# PowerSupply_Schematic.net
KiCad netlist of a schematic drawn in Altium Designer
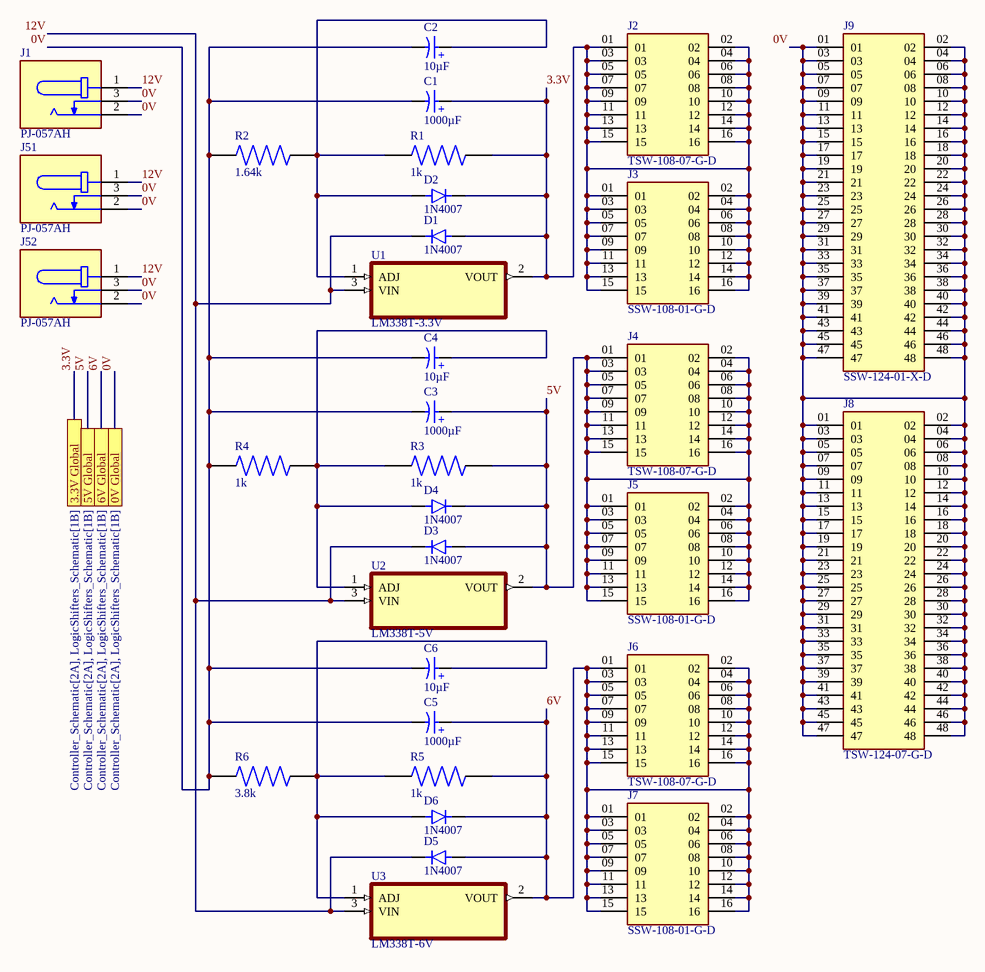
[diagram p0: PowerSupply_Schematic.SchDoc]

(export (version "E")
  (design (tool "Eeschema 10.0.6"))
  (components
    (comp (ref "C1")
      (value "1000µF")
      (footprint "WCAP-ATG5_D10H12.5")
      (description "WCAP-ATG5 Aluminum Electrolytic Capacitor, Radial, THT, D10 x H12.5mm, 1000µF, 16V")
      (fields
        (field (name "MANUFACTURER PART NUMBER") "860020375017")
        (field (name "MANUFACTURER") "Wurth Elektronik")
      )
      (libsource (lib "CAP-DIP-1000uF-16V") (part "860020375017"))
    )
    (comp (ref "C2")
      (value "10µF")
      (footprint "WCAP-ATG5_D5H11")
      (description "WCAP-ATG5 Aluminum Electrolytic Capacitor, Radial, THT, D5 x H11mm, 10µF, 16V")
      (fields
        (field (name "MANUFACTURER PART NUMBER") "860020372001")
        (field (name "MANUFACTURER") "Wurth Elektronik")
      )
      (libsource (lib "CAP-DIP-1000uF-16V") (part "860020372001"))
    )
    (comp (ref "C3")
      (value "1000µF")
      (footprint "WCAP-ATG5_D10H12.5")
      (description "WCAP-ATG5 Aluminum Electrolytic Capacitor, Radial, THT, D10 x H12.5mm, 1000µF, 16V")
      (fields
        (field (name "MANUFACTURER PART NUMBER") "860020375017")
        (field (name "MANUFACTURER") "Wurth Elektronik")
      )
      (libsource (lib "CAP-DIP-1000uF-16V") (part "860020375017"))
    )
    (comp (ref "C4")
      (value "10µF")
      (footprint "WCAP-ATG5_D5H11")
      (description "WCAP-ATG5 Aluminum Electrolytic Capacitor, Radial, THT, D5 x H11mm, 10µF, 16V")
      (fields
        (field (name "MANUFACTURER PART NUMBER") "860020372001")
        (field (name "MANUFACTURER") "Wurth Elektronik")
      )
      (libsource (lib "CAP-DIP-1000uF-16V") (part "860020372001"))
    )
    (comp (ref "C5")
      (value "1000µF")
      (footprint "WCAP-ATG5_D10H12.5")
      (description "WCAP-ATG5 Aluminum Electrolytic Capacitor, Radial, THT, D10 x H12.5mm, 1000µF, 16V")
      (fields
        (field (name "MANUFACTURER PART NUMBER") "860020375017")
        (field (name "MANUFACTURER") "Wurth Elektronik")
      )
      (libsource (lib "CAP-DIP-1000uF-16V") (part "860020375017"))
    )
    (comp (ref "C6")
      (value "10µF")
      (footprint "WCAP-ATG5_D5H11")
      (description "WCAP-ATG5 Aluminum Electrolytic Capacitor, Radial, THT, D5 x H11mm, 10µF, 16V")
      (fields
        (field (name "MANUFACTURER PART NUMBER") "860020372001")
        (field (name "MANUFACTURER") "Wurth Elektronik")
      )
      (libsource (lib "CAP-DIP-1000uF-16V") (part "860020372001"))
    )
    (comp (ref "D1")
      (value "1N4007")
      (footprint "DIOAD1060W80L520D270")
      (description "Rectifier Silicon, 1000V, 1 A, DO-41 Case, Solder Leads, 1N Series ¦ NTE Electronics Inc. 1N4007")
      (fields (field (name "MF") "NTE Electronics, Inc."))
      (libsource (lib "DO-41") (part "1N4007"))
    )
    (comp (ref "D2")
      (value "1N4007")
      (footprint "DIOAD1060W80L520D270")
      (description "Rectifier Silicon, 1000V, 1 A, DO-41 Case, Solder Leads, 1N Series ¦ NTE Electronics Inc. 1N4007")
      (fields (field (name "MF") "NTE Electronics, Inc."))
      (libsource (lib "DO-41") (part "1N4007"))
    )
    (comp (ref "D3")
      (value "1N4007")
      (footprint "DIOAD1060W80L520D270")
      (description "Rectifier Silicon, 1000V, 1 A, DO-41 Case, Solder Leads, 1N Series ¦ NTE Electronics Inc. 1N4007")
      (fields (field (name "MF") "NTE Electronics, Inc."))
      (libsource (lib "DO-41") (part "1N4007"))
    )
    (comp (ref "D4")
      (value "1N4007")
      (footprint "DIOAD1060W80L520D270")
      (description "Rectifier Silicon, 1000V, 1 A, DO-41 Case, Solder Leads, 1N Series ¦ NTE Electronics Inc. 1N4007")
      (fields (field (name "MF") "NTE Electronics, Inc."))
      (libsource (lib "DO-41") (part "1N4007"))
    )
    (comp (ref "D5")
      (value "1N4007")
      (footprint "DIOAD1060W80L520D270")
      (description "Rectifier Silicon, 1000V, 1 A, DO-41 Case, Solder Leads, 1N Series ¦ NTE Electronics Inc. 1N4007")
      (fields (field (name "MF") "NTE Electronics, Inc."))
      (libsource (lib "DO-41") (part "1N4007"))
    )
    (comp (ref "D6")
      (value "1N4007")
      (footprint "DIOAD1060W80L520D270")
      (description "Rectifier Silicon, 1000V, 1 A, DO-41 Case, Solder Leads, 1N Series ¦ NTE Electronics Inc. 1N4007")
      (fields (field (name "MF") "NTE Electronics, Inc."))
      (libsource (lib "DO-41") (part "1N4007"))
    )
    (comp (ref "J1")
      (value "PJ-057AH")
      (footprint "CUI_PJ-057AH")
      (description "2.0 x 6.3 mm, 5.0 A, Horizontal, Through Hole, Pick-n-Place Top, Dc Power Jack Connector")
      (fields (field (name "MF") "Same Sky"))
      (libsource (lib "PowerJack-2mm-6.3mm") (part "PJ-057AH"))
    )
    (comp (ref "J2")
      (value "TSW-108-07-G-D")
      (footprint "SAMTEC_TSW-108-07-G-D")
      (fields (field (name "MF") "Samtec"))
      (libsource (lib "TSW-108-07-G-D") (part "TSW-108-07-G-D"))
    )
    (comp (ref "J3")
      (value "SSW-108-01-G-D")
      (footprint "SAMTEC_SSW-108-01-G-D")
      (fields (field (name "MF") "Samtec"))
      (libsource (lib "SSW-108-01-G-D") (part "SSW-108-01-G-D"))
    )
    (comp (ref "J4")
      (value "TSW-108-07-G-D")
      (footprint "SAMTEC_TSW-108-07-G-D")
      (fields (field (name "MF") "Samtec"))
      (libsource (lib "TSW-108-07-G-D") (part "TSW-108-07-G-D"))
    )
    (comp (ref "J5")
      (value "SSW-108-01-G-D")
      (footprint "SAMTEC_SSW-108-01-G-D")
      (fields (field (name "MF") "Samtec"))
      (libsource (lib "SSW-108-01-G-D") (part "SSW-108-01-G-D"))
    )
    (comp (ref "J6")
      (value "TSW-108-07-G-D")
      (footprint "SAMTEC_TSW-108-07-G-D")
      (fields (field (name "MF") "Samtec"))
      (libsource (lib "TSW-108-07-G-D") (part "TSW-108-07-G-D"))
    )
    (comp (ref "J7")
      (value "SSW-108-01-G-D")
      (footprint "SAMTEC_SSW-108-01-G-D")
      (fields (field (name "MF") "Samtec"))
      (libsource (lib "SSW-108-01-G-D") (part "SSW-108-01-G-D"))
    )
    (comp (ref "J8")
      (value "TSW-124-07-G-D")
      (footprint "SAMTEC_TSW-124-07-G-D")
      (fields (field (name "MF") "Samtec"))
      (libsource (lib "TSW-124-07-G-D") (part "TSW-124-07-G-D"))
    )
    (comp (ref "J9")
      (value "SSW-124-01-X-D")
      (footprint "SAMTEC_SSW-124-01-X-D")
      (fields (field (name "MF") "Samtec"))
      (libsource (lib "SSW-124-01-G-D") (part "SSW-124-01-X-D"))
    )
    (comp (ref "J51")
      (value "PJ-057AH")
      (footprint "CUI_PJ-057AH")
      (description "2.0 x 6.3 mm, 5.0 A, Horizontal, Through Hole, Pick-n-Place Top, Dc Power Jack Connector")
      (fields (field (name "MF") "Same Sky"))
      (libsource (lib "PowerJack-2mm-6.3mm") (part "PJ-057AH"))
    )
    (comp (ref "J52")
      (value "PJ-057AH")
      (footprint "CUI_PJ-057AH")
      (description "2.0 x 6.3 mm, 5.0 A, Horizontal, Through Hole, Pick-n-Place Top, Dc Power Jack Connector")
      (fields (field (name "MF") "Same Sky"))
      (libsource (lib "PowerJack-2mm-6.3mm") (part "PJ-057AH"))
    )
    (comp (ref "R1")
      (value "1k")
      (footprint "RESAD700W45L350D185")
      (description "1 MOhms Â±5% 0.25W, 1/4W Through Hole Resistor Axial - Carbon Film")
      (fields (field (name "MF") "TE Connectivity") (field (name "MP") "3-1623927-1"))
      (libsource (lib "RES-DIP-0.25W") (part "3-1623927-1"))
    )
    (comp (ref "R2")
      (value "1.64k")
      (footprint "RESAD700W45L350D185")
      (description "1 MOhms Â±5% 0.25W, 1/4W Through Hole Resistor Axial - Carbon Film")
      (fields (field (name "MF") "TE Connectivity") (field (name "MP") "3-1623927-1"))
      (libsource (lib "RES-DIP-0.25W") (part "3-1623927-1"))
    )
    (comp (ref "R3")
      (value "1k")
      (footprint "RESAD700W45L350D185")
      (description "1 MOhms Â±5% 0.25W, 1/4W Through Hole Resistor Axial - Carbon Film")
      (fields (field (name "MF") "TE Connectivity") (field (name "MP") "3-1623927-1"))
      (libsource (lib "RES-DIP-0.25W") (part "3-1623927-1"))
    )
    (comp (ref "R4")
      (value "1k")
      (footprint "RESAD700W45L350D185")
      (description "1 MOhms Â±5% 0.25W, 1/4W Through Hole Resistor Axial - Carbon Film")
      (fields (field (name "MF") "TE Connectivity") (field (name "MP") "3-1623927-1"))
      (libsource (lib "RES-DIP-0.25W") (part "3-1623927-1"))
    )
    (comp (ref "R5")
      (value "1k")
      (footprint "RESAD700W45L350D185")
      (description "1 MOhms Â±5% 0.25W, 1/4W Through Hole Resistor Axial - Carbon Film")
      (fields (field (name "MF") "TE Connectivity") (field (name "MP") "3-1623927-1"))
      (libsource (lib "RES-DIP-0.25W") (part "3-1623927-1"))
    )
    (comp (ref "R6")
      (value "3.8k")
      (footprint "RESAD700W45L350D185")
      (description "1 MOhms Â±5% 0.25W, 1/4W Through Hole Resistor Axial - Carbon Film")
      (fields (field (name "MF") "TE Connectivity") (field (name "MP") "3-1623927-1"))
      (libsource (lib "RES-DIP-0.25W") (part "3-1623927-1"))
    )
    (comp (ref "U1")
      (value "LM338T-3.3V")
      (footprint "TO254P1054X470X1955-3")
      (description "5-A, 40-V, low-IQ, adjustable linear voltage regulator 3-TO-220 0 to 125")
      (fields (field (name "MF") "Texas Instruments") (field (name "MP") "LM338T"))
      (libsource (lib "LM338T") (part "LM338T"))
    )
    (comp (ref "U2")
      (value "LM338T-5V")
      (footprint "TO254P1054X470X1955-3")
      (description "5-A, 40-V, low-IQ, adjustable linear voltage regulator 3-TO-220 0 to 125")
      (fields (field (name "MF") "Texas Instruments") (field (name "MP") "LM338T"))
      (libsource (lib "LM338T") (part "LM338T"))
    )
    (comp (ref "U3")
      (value "LM338T-6V")
      (footprint "TO254P1054X470X1955-3")
      (description "5-A, 40-V, low-IQ, adjustable linear voltage regulator 3-TO-220 0 to 125")
      (fields (field (name "MF") "Texas Instruments") (field (name "MP") "LM338T"))
      (libsource (lib "LM338T") (part "LM338T"))
    )
  )
  (nets
    (net (code "1") (name "/0V") (class "Default")
      (node (ref "C1") (pin "2") (pinfunction "N_2") (pintype "passive"))
      (node (ref "C2") (pin "2") (pinfunction "N_2") (pintype "passive"))
      (node (ref "C3") (pin "2") (pinfunction "N_2") (pintype "passive"))
      (node (ref "C4") (pin "2") (pinfunction "N_2") (pintype "passive"))
      (node (ref "C5") (pin "2") (pinfunction "N_2") (pintype "passive"))
      (node (ref "C6") (pin "2") (pinfunction "N_2") (pintype "passive"))
      (node (ref "J1") (pin "2") (pinfunction "2_2") (pintype "passive"))
      (node (ref "J1") (pin "3") (pinfunction "3_3") (pintype "passive"))
      (node (ref "J51") (pin "2") (pinfunction "2_2") (pintype "passive"))
      (node (ref "J51") (pin "3") (pinfunction "3_3") (pintype "passive"))
      (node (ref "J52") (pin "2") (pinfunction "2_2") (pintype "passive"))
      (node (ref "J52") (pin "3") (pinfunction "3_3") (pintype "passive"))
      (node (ref "J8") (pin "01") (pinfunction "01_01") (pintype "passive"))
      (node (ref "J8") (pin "02") (pinfunction "02_02") (pintype "passive"))
      (node (ref "J8") (pin "03") (pinfunction "03_03") (pintype "passive"))
      (node (ref "J8") (pin "04") (pinfunction "04_04") (pintype "passive"))
      (node (ref "J8") (pin "05") (pinfunction "05_05") (pintype "passive"))
      (node (ref "J8") (pin "06") (pinfunction "06_06") (pintype "passive"))
      (node (ref "J8") (pin "07") (pinfunction "07_07") (pintype "passive"))
      (node (ref "J8") (pin "08") (pinfunction "08_08") (pintype "passive"))
      (node (ref "J8") (pin "09") (pinfunction "09_09") (pintype "passive"))
      (node (ref "J8") (pin "10") (pinfunction "10_10") (pintype "passive"))
      (node (ref "J8") (pin "11") (pinfunction "11_11") (pintype "passive"))
      (node (ref "J8") (pin "12") (pinfunction "12_12") (pintype "passive"))
      (node (ref "J8") (pin "13") (pinfunction "13_13") (pintype "passive"))
      (node (ref "J8") (pin "14") (pinfunction "14_14") (pintype "passive"))
      (node (ref "J8") (pin "15") (pinfunction "15_15") (pintype "passive"))
      (node (ref "J8") (pin "16") (pinfunction "16_16") (pintype "passive"))
      (node (ref "J8") (pin "17") (pinfunction "17_17") (pintype "passive"))
      (node (ref "J8") (pin "18") (pinfunction "18_18") (pintype "passive"))
      (node (ref "J8") (pin "19") (pinfunction "19_19") (pintype "passive"))
      (node (ref "J8") (pin "20") (pinfunction "20_20") (pintype "passive"))
      (node (ref "J8") (pin "21") (pinfunction "21_21") (pintype "passive"))
      (node (ref "J8") (pin "22") (pinfunction "22_22") (pintype "passive"))
      (node (ref "J8") (pin "23") (pinfunction "23_23") (pintype "passive"))
      (node (ref "J8") (pin "24") (pinfunction "24_24") (pintype "passive"))
      (node (ref "J8") (pin "25") (pinfunction "25_25") (pintype "passive"))
      (node (ref "J8") (pin "26") (pinfunction "26_26") (pintype "passive"))
      (node (ref "J8") (pin "27") (pinfunction "27_27") (pintype "passive"))
      (node (ref "J8") (pin "28") (pinfunction "28_28") (pintype "passive"))
      (node (ref "J8") (pin "29") (pinfunction "29_29") (pintype "passive"))
      (node (ref "J8") (pin "30") (pinfunction "30_30") (pintype "passive"))
      (node (ref "J8") (pin "31") (pinfunction "31_31") (pintype "passive"))
      (node (ref "J8") (pin "32") (pinfunction "32_32") (pintype "passive"))
      (node (ref "J8") (pin "33") (pinfunction "33_33") (pintype "passive"))
      (node (ref "J8") (pin "34") (pinfunction "34_34") (pintype "passive"))
      (node (ref "J8") (pin "35") (pinfunction "35_35") (pintype "passive"))
      (node (ref "J8") (pin "36") (pinfunction "36_36") (pintype "passive"))
      (node (ref "J8") (pin "37") (pinfunction "37_37") (pintype "passive"))
      (node (ref "J8") (pin "38") (pinfunction "38_38") (pintype "passive"))
      (node (ref "J8") (pin "39") (pinfunction "39_39") (pintype "passive"))
      (node (ref "J8") (pin "40") (pinfunction "40_40") (pintype "passive"))
      (node (ref "J8") (pin "41") (pinfunction "41_41") (pintype "passive"))
      (node (ref "J8") (pin "42") (pinfunction "42_42") (pintype "passive"))
      (node (ref "J8") (pin "43") (pinfunction "43_43") (pintype "passive"))
      (node (ref "J8") (pin "44") (pinfunction "44_44") (pintype "passive"))
      (node (ref "J8") (pin "45") (pinfunction "45_45") (pintype "passive"))
      (node (ref "J8") (pin "46") (pinfunction "46_46") (pintype "passive"))
      (node (ref "J8") (pin "47") (pinfunction "47_47") (pintype "passive"))
      (node (ref "J8") (pin "48") (pinfunction "48_48") (pintype "passive"))
      (node (ref "J9") (pin "01") (pinfunction "01_01") (pintype "passive"))
      (node (ref "J9") (pin "02") (pinfunction "02_02") (pintype "passive"))
      (node (ref "J9") (pin "03") (pinfunction "03_03") (pintype "passive"))
      (node (ref "J9") (pin "04") (pinfunction "04_04") (pintype "passive"))
      (node (ref "J9") (pin "05") (pinfunction "05_05") (pintype "passive"))
      (node (ref "J9") (pin "06") (pinfunction "06_06") (pintype "passive"))
      (node (ref "J9") (pin "07") (pinfunction "07_07") (pintype "passive"))
      (node (ref "J9") (pin "08") (pinfunction "08_08") (pintype "passive"))
      (node (ref "J9") (pin "09") (pinfunction "09_09") (pintype "passive"))
      (node (ref "J9") (pin "10") (pinfunction "10_10") (pintype "passive"))
      (node (ref "J9") (pin "11") (pinfunction "11_11") (pintype "passive"))
      (node (ref "J9") (pin "12") (pinfunction "12_12") (pintype "passive"))
      (node (ref "J9") (pin "13") (pinfunction "13_13") (pintype "passive"))
      (node (ref "J9") (pin "14") (pinfunction "14_14") (pintype "passive"))
      (node (ref "J9") (pin "15") (pinfunction "15_15") (pintype "passive"))
      (node (ref "J9") (pin "16") (pinfunction "16_16") (pintype "passive"))
      (node (ref "J9") (pin "17") (pinfunction "17_17") (pintype "passive"))
      (node (ref "J9") (pin "18") (pinfunction "18_18") (pintype "passive"))
      (node (ref "J9") (pin "19") (pinfunction "19_19") (pintype "passive"))
      (node (ref "J9") (pin "20") (pinfunction "20_20") (pintype "passive"))
      (node (ref "J9") (pin "21") (pinfunction "21_21") (pintype "passive"))
      (node (ref "J9") (pin "22") (pinfunction "22_22") (pintype "passive"))
      (node (ref "J9") (pin "23") (pinfunction "23_23") (pintype "passive"))
      (node (ref "J9") (pin "24") (pinfunction "24_24") (pintype "passive"))
      (node (ref "J9") (pin "25") (pinfunction "25_25") (pintype "passive"))
      (node (ref "J9") (pin "26") (pinfunction "26_26") (pintype "passive"))
      (node (ref "J9") (pin "27") (pinfunction "27_27") (pintype "passive"))
      (node (ref "J9") (pin "28") (pinfunction "28_28") (pintype "passive"))
      (node (ref "J9") (pin "29") (pinfunction "29_29") (pintype "passive"))
      (node (ref "J9") (pin "30") (pinfunction "30_30") (pintype "passive"))
      (node (ref "J9") (pin "31") (pinfunction "31_31") (pintype "passive"))
      (node (ref "J9") (pin "32") (pinfunction "32_32") (pintype "passive"))
      (node (ref "J9") (pin "33") (pinfunction "33_33") (pintype "passive"))
      (node (ref "J9") (pin "34") (pinfunction "34_34") (pintype "passive"))
      (node (ref "J9") (pin "35") (pinfunction "35_35") (pintype "passive"))
      (node (ref "J9") (pin "36") (pinfunction "36_36") (pintype "passive"))
      (node (ref "J9") (pin "37") (pinfunction "37_37") (pintype "passive"))
      (node (ref "J9") (pin "38") (pinfunction "38_38") (pintype "passive"))
      (node (ref "J9") (pin "39") (pinfunction "39_39") (pintype "passive"))
      (node (ref "J9") (pin "40") (pinfunction "40_40") (pintype "passive"))
      (node (ref "J9") (pin "41") (pinfunction "41_41") (pintype "passive"))
      (node (ref "J9") (pin "42") (pinfunction "42_42") (pintype "passive"))
      (node (ref "J9") (pin "43") (pinfunction "43_43") (pintype "passive"))
      (node (ref "J9") (pin "44") (pinfunction "44_44") (pintype "passive"))
      (node (ref "J9") (pin "45") (pinfunction "45_45") (pintype "passive"))
      (node (ref "J9") (pin "46") (pinfunction "46_46") (pintype "passive"))
      (node (ref "J9") (pin "47") (pinfunction "47_47") (pintype "passive"))
      (node (ref "J9") (pin "48") (pinfunction "48_48") (pintype "passive"))
      (node (ref "R2") (pin "1") (pinfunction "1_1") (pintype "passive"))
      (node (ref "R4") (pin "1") (pinfunction "1_1") (pintype "passive"))
      (node (ref "R6") (pin "1") (pinfunction "1_1") (pintype "passive"))
    )
    (net (code "2") (name "/3.3V") (class "Default")
      (node (ref "C1") (pin "1") (pinfunction "P_1") (pintype "passive"))
      (node (ref "D1") (pin "A") (pinfunction "A_A") (pintype "passive"))
      (node (ref "D2") (pin "C") (pinfunction "C_C") (pintype "passive"))
      (node (ref "J2") (pin "01") (pinfunction "01_01") (pintype "passive"))
      (node (ref "J2") (pin "02") (pinfunction "02_02") (pintype "passive"))
      (node (ref "J2") (pin "03") (pinfunction "03_03") (pintype "passive"))
      (node (ref "J2") (pin "04") (pinfunction "04_04") (pintype "passive"))
      (node (ref "J2") (pin "05") (pinfunction "05_05") (pintype "passive"))
      (node (ref "J2") (pin "06") (pinfunction "06_06") (pintype "passive"))
      (node (ref "J2") (pin "07") (pinfunction "07_07") (pintype "passive"))
      (node (ref "J2") (pin "08") (pinfunction "08_08") (pintype "passive"))
      (node (ref "J2") (pin "09") (pinfunction "09_09") (pintype "passive"))
      (node (ref "J2") (pin "10") (pinfunction "10_10") (pintype "passive"))
      (node (ref "J2") (pin "11") (pinfunction "11_11") (pintype "passive"))
      (node (ref "J2") (pin "12") (pinfunction "12_12") (pintype "passive"))
      (node (ref "J2") (pin "13") (pinfunction "13_13") (pintype "passive"))
      (node (ref "J2") (pin "14") (pinfunction "14_14") (pintype "passive"))
      (node (ref "J2") (pin "15") (pinfunction "15_15") (pintype "passive"))
      (node (ref "J2") (pin "16") (pinfunction "16_16") (pintype "passive"))
      (node (ref "J3") (pin "01") (pinfunction "01_01") (pintype "passive"))
      (node (ref "J3") (pin "02") (pinfunction "02_02") (pintype "passive"))
      (node (ref "J3") (pin "03") (pinfunction "03_03") (pintype "passive"))
      (node (ref "J3") (pin "04") (pinfunction "04_04") (pintype "passive"))
      (node (ref "J3") (pin "05") (pinfunction "05_05") (pintype "passive"))
      (node (ref "J3") (pin "06") (pinfunction "06_06") (pintype "passive"))
      (node (ref "J3") (pin "07") (pinfunction "07_07") (pintype "passive"))
      (node (ref "J3") (pin "08") (pinfunction "08_08") (pintype "passive"))
      (node (ref "J3") (pin "09") (pinfunction "09_09") (pintype "passive"))
      (node (ref "J3") (pin "10") (pinfunction "10_10") (pintype "passive"))
      (node (ref "J3") (pin "11") (pinfunction "11_11") (pintype "passive"))
      (node (ref "J3") (pin "12") (pinfunction "12_12") (pintype "passive"))
      (node (ref "J3") (pin "13") (pinfunction "13_13") (pintype "passive"))
      (node (ref "J3") (pin "14") (pinfunction "14_14") (pintype "passive"))
      (node (ref "J3") (pin "15") (pinfunction "15_15") (pintype "passive"))
      (node (ref "J3") (pin "16") (pinfunction "16_16") (pintype "passive"))
      (node (ref "R1") (pin "2") (pinfunction "2_2") (pintype "passive"))
      (node (ref "U1") (pin "2") (pinfunction "VOUT_2") (pintype "output"))
    )
    (net (code "3") (name "/5V") (class "Default")
      (node (ref "C3") (pin "1") (pinfunction "P_1") (pintype "passive"))
      (node (ref "D3") (pin "A") (pinfunction "A_A") (pintype "passive"))
      (node (ref "D4") (pin "C") (pinfunction "C_C") (pintype "passive"))
      (node (ref "J4") (pin "01") (pinfunction "01_01") (pintype "passive"))
      (node (ref "J4") (pin "02") (pinfunction "02_02") (pintype "passive"))
      (node (ref "J4") (pin "03") (pinfunction "03_03") (pintype "passive"))
      (node (ref "J4") (pin "04") (pinfunction "04_04") (pintype "passive"))
      (node (ref "J4") (pin "05") (pinfunction "05_05") (pintype "passive"))
      (node (ref "J4") (pin "06") (pinfunction "06_06") (pintype "passive"))
      (node (ref "J4") (pin "07") (pinfunction "07_07") (pintype "passive"))
      (node (ref "J4") (pin "08") (pinfunction "08_08") (pintype "passive"))
      (node (ref "J4") (pin "09") (pinfunction "09_09") (pintype "passive"))
      (node (ref "J4") (pin "10") (pinfunction "10_10") (pintype "passive"))
      (node (ref "J4") (pin "11") (pinfunction "11_11") (pintype "passive"))
      (node (ref "J4") (pin "12") (pinfunction "12_12") (pintype "passive"))
      (node (ref "J4") (pin "13") (pinfunction "13_13") (pintype "passive"))
      (node (ref "J4") (pin "14") (pinfunction "14_14") (pintype "passive"))
      (node (ref "J4") (pin "15") (pinfunction "15_15") (pintype "passive"))
      (node (ref "J4") (pin "16") (pinfunction "16_16") (pintype "passive"))
      (node (ref "J5") (pin "01") (pinfunction "01_01") (pintype "passive"))
      (node (ref "J5") (pin "02") (pinfunction "02_02") (pintype "passive"))
      (node (ref "J5") (pin "03") (pinfunction "03_03") (pintype "passive"))
      (node (ref "J5") (pin "04") (pinfunction "04_04") (pintype "passive"))
      (node (ref "J5") (pin "05") (pinfunction "05_05") (pintype "passive"))
      (node (ref "J5") (pin "06") (pinfunction "06_06") (pintype "passive"))
      (node (ref "J5") (pin "07") (pinfunction "07_07") (pintype "passive"))
      (node (ref "J5") (pin "08") (pinfunction "08_08") (pintype "passive"))
      (node (ref "J5") (pin "09") (pinfunction "09_09") (pintype "passive"))
      (node (ref "J5") (pin "10") (pinfunction "10_10") (pintype "passive"))
      (node (ref "J5") (pin "11") (pinfunction "11_11") (pintype "passive"))
      (node (ref "J5") (pin "12") (pinfunction "12_12") (pintype "passive"))
      (node (ref "J5") (pin "13") (pinfunction "13_13") (pintype "passive"))
      (node (ref "J5") (pin "14") (pinfunction "14_14") (pintype "passive"))
      (node (ref "J5") (pin "15") (pinfunction "15_15") (pintype "passive"))
      (node (ref "J5") (pin "16") (pinfunction "16_16") (pintype "passive"))
      (node (ref "R3") (pin "2") (pinfunction "2_2") (pintype "passive"))
      (node (ref "U2") (pin "2") (pinfunction "VOUT_2") (pintype "output"))
    )
    (net (code "4") (name "/6V") (class "Default")
      (node (ref "C5") (pin "1") (pinfunction "P_1") (pintype "passive"))
      (node (ref "D5") (pin "A") (pinfunction "A_A") (pintype "passive"))
      (node (ref "D6") (pin "C") (pinfunction "C_C") (pintype "passive"))
      (node (ref "J6") (pin "01") (pinfunction "01_01") (pintype "passive"))
      (node (ref "J6") (pin "02") (pinfunction "02_02") (pintype "passive"))
      (node (ref "J6") (pin "03") (pinfunction "03_03") (pintype "passive"))
      (node (ref "J6") (pin "04") (pinfunction "04_04") (pintype "passive"))
      (node (ref "J6") (pin "05") (pinfunction "05_05") (pintype "passive"))
      (node (ref "J6") (pin "06") (pinfunction "06_06") (pintype "passive"))
      (node (ref "J6") (pin "07") (pinfunction "07_07") (pintype "passive"))
      (node (ref "J6") (pin "08") (pinfunction "08_08") (pintype "passive"))
      (node (ref "J6") (pin "09") (pinfunction "09_09") (pintype "passive"))
      (node (ref "J6") (pin "10") (pinfunction "10_10") (pintype "passive"))
      (node (ref "J6") (pin "11") (pinfunction "11_11") (pintype "passive"))
      (node (ref "J6") (pin "12") (pinfunction "12_12") (pintype "passive"))
      (node (ref "J6") (pin "13") (pinfunction "13_13") (pintype "passive"))
      (node (ref "J6") (pin "14") (pinfunction "14_14") (pintype "passive"))
      (node (ref "J6") (pin "15") (pinfunction "15_15") (pintype "passive"))
      (node (ref "J6") (pin "16") (pinfunction "16_16") (pintype "passive"))
      (node (ref "J7") (pin "01") (pinfunction "01_01") (pintype "passive"))
      (node (ref "J7") (pin "02") (pinfunction "02_02") (pintype "passive"))
      (node (ref "J7") (pin "03") (pinfunction "03_03") (pintype "passive"))
      (node (ref "J7") (pin "04") (pinfunction "04_04") (pintype "passive"))
      (node (ref "J7") (pin "05") (pinfunction "05_05") (pintype "passive"))
      (node (ref "J7") (pin "06") (pinfunction "06_06") (pintype "passive"))
      (node (ref "J7") (pin "07") (pinfunction "07_07") (pintype "passive"))
      (node (ref "J7") (pin "08") (pinfunction "08_08") (pintype "passive"))
      (node (ref "J7") (pin "09") (pinfunction "09_09") (pintype "passive"))
      (node (ref "J7") (pin "10") (pinfunction "10_10") (pintype "passive"))
      (node (ref "J7") (pin "11") (pinfunction "11_11") (pintype "passive"))
      (node (ref "J7") (pin "12") (pinfunction "12_12") (pintype "passive"))
      (node (ref "J7") (pin "13") (pinfunction "13_13") (pintype "passive"))
      (node (ref "J7") (pin "14") (pinfunction "14_14") (pintype "passive"))
      (node (ref "J7") (pin "15") (pinfunction "15_15") (pintype "passive"))
      (node (ref "J7") (pin "16") (pinfunction "16_16") (pintype "passive"))
      (node (ref "R5") (pin "2") (pinfunction "2_2") (pintype "passive"))
      (node (ref "U3") (pin "2") (pinfunction "VOUT_2") (pintype "output"))
    )
    (net (code "5") (name "/12V") (class "Default")
      (node (ref "D1") (pin "C") (pinfunction "C_C") (pintype "passive"))
      (node (ref "D3") (pin "C") (pinfunction "C_C") (pintype "passive"))
      (node (ref "D5") (pin "C") (pinfunction "C_C") (pintype "passive"))
      (node (ref "J1") (pin "1") (pinfunction "1_1") (pintype "passive"))
      (node (ref "J51") (pin "1") (pinfunction "1_1") (pintype "passive"))
      (node (ref "J52") (pin "1") (pinfunction "1_1") (pintype "passive"))
      (node (ref "U1") (pin "3") (pinfunction "VIN_3") (pintype "input"))
      (node (ref "U2") (pin "3") (pinfunction "VIN_3") (pintype "input"))
      (node (ref "U3") (pin "3") (pinfunction "VIN_3") (pintype "input"))
    )
    (net (code "6") (name "Net-(C2-P)") (class "Default")
      (node (ref "C2") (pin "1") (pinfunction "P_1") (pintype "passive"))
      (node (ref "D2") (pin "A") (pinfunction "A_A") (pintype "passive"))
      (node (ref "R1") (pin "1") (pinfunction "1_1") (pintype "passive"))
      (node (ref "R2") (pin "2") (pinfunction "2_2") (pintype "passive"))
      (node (ref "U1") (pin "1") (pinfunction "ADJ_1") (pintype "input"))
    )
    (net (code "7") (name "Net-(C4-P)") (class "Default")
      (node (ref "C4") (pin "1") (pinfunction "P_1") (pintype "passive"))
      (node (ref "D4") (pin "A") (pinfunction "A_A") (pintype "passive"))
      (node (ref "R3") (pin "1") (pinfunction "1_1") (pintype "passive"))
      (node (ref "R4") (pin "2") (pinfunction "2_2") (pintype "passive"))
      (node (ref "U2") (pin "1") (pinfunction "ADJ_1") (pintype "input"))
    )
    (net (code "8") (name "Net-(C6-P)") (class "Default")
      (node (ref "C6") (pin "1") (pinfunction "P_1") (pintype "passive"))
      (node (ref "D6") (pin "A") (pinfunction "A_A") (pintype "passive"))
      (node (ref "R5") (pin "1") (pinfunction "1_1") (pintype "passive"))
      (node (ref "R6") (pin "2") (pinfunction "2_2") (pintype "passive"))
      (node (ref "U3") (pin "1") (pinfunction "ADJ_1") (pintype "input"))
    )
  )
)
